# buck4.net
KiCad netlist of a schematic drawn in Altium Designer
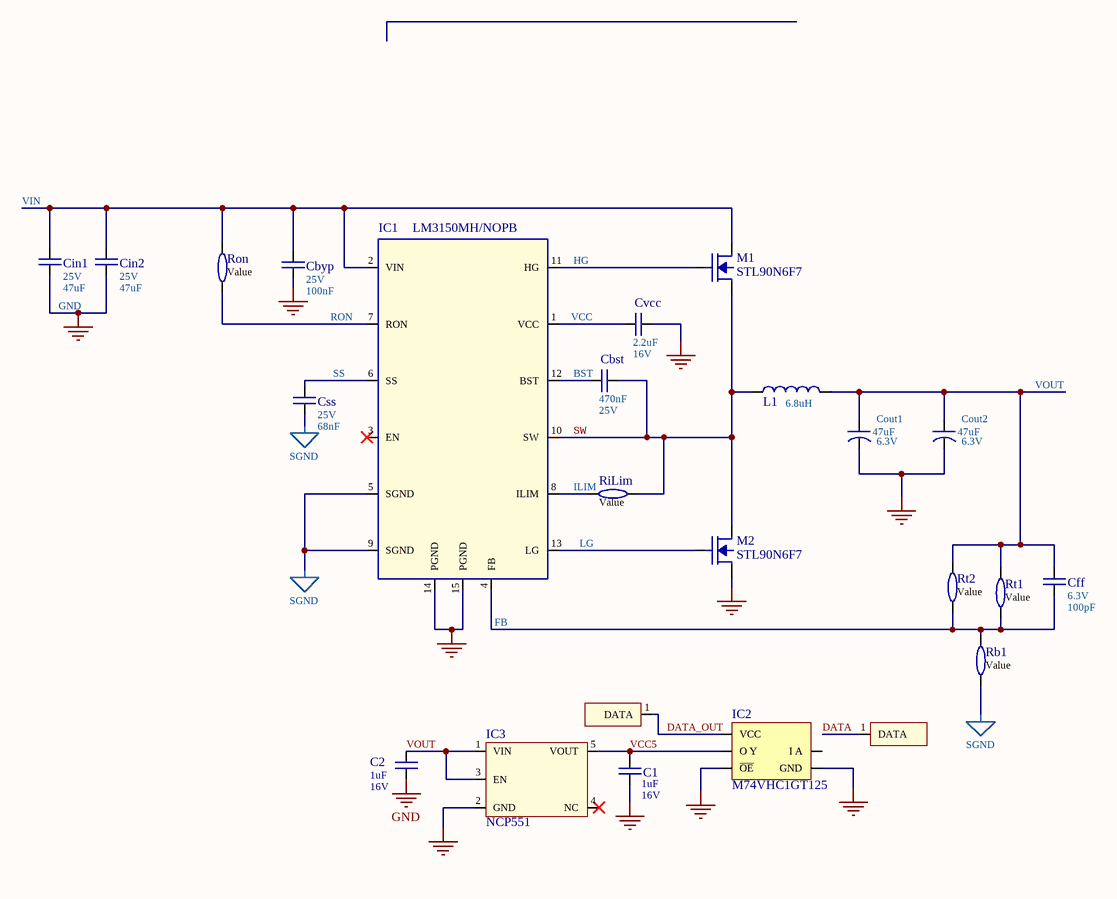
[diagram p0: buck4.schdoc]

(export (version "E")
  (design (tool "Eeschema 10.0.6"))
  (components
    (comp (ref "C1")
      (value "1uF")
      (footprint "CAPC1608X08L")
      (description "Multilayer Ceramic Capacitor")
      (fields (field (name "VOLTAGE") "16V") (field (name "Comment") "MLCC"))
      (libsource (lib "buck4") (part "MLCC"))
    )
    (comp (ref "C2")
      (value "1uF")
      (footprint "CAPC1608X08L")
      (description "Multilayer Ceramic Capacitor")
      (fields (field (name "VOLTAGE") "16V") (field (name "Comment") "MLCC"))
      (libsource (lib "buck4") (part "MLCC"))
    )
    (comp (ref "Cbst")
      (value "470nF")
      (footprint "CAPC1608X08L")
      (description "Multilayer Ceramic Capacitor")
      (fields (field (name "VOLTAGE") "25V") (field (name "Comment") "MLCC"))
      (libsource (lib "buck4") (part "MLCC"))
    )
    (comp (ref "Cbyp")
      (value "100nF")
      (footprint "CAPC2012X12L")
      (description "Multilayer Ceramic Capacitor")
      (fields (field (name "VOLTAGE") "25V") (field (name "Comment") "MLCC"))
      (libsource (lib "buck4") (part "MLCC"))
    )
    (comp (ref "Cff")
      (value "100pF")
      (footprint "CAPC1608X08L")
      (description "Multilayer Ceramic Capacitor")
      (fields (field (name "VOLTAGE") "6.3V") (field (name "Comment") "MLCC"))
      (libsource (lib "buck4") (part "MLCC"))
    )
    (comp (ref "Cin1")
      (value "47uF")
      (footprint "CAPC3225X25L")
      (description "Multilayer Ceramic Capacitor")
      (fields
        (field (name "MPN") "C3216X5R1E476M160AC")
        (field (name "VOLTAGE") "25V")
        (field (name "Comment") "MLCC")
      )
      (libsource (lib "buck4") (part "MLCC"))
    )
    (comp (ref "Cin2")
      (value "47uF")
      (footprint "CAPC3225X25L")
      (description "Multilayer Ceramic Capacitor")
      (fields
        (field (name "MPN") "C3216X5R1E476M160AC")
        (field (name "VOLTAGE") "25V")
        (field (name "Comment") "MLCC")
      )
      (libsource (lib "buck4") (part "MLCC"))
    )
    (comp (ref "Cout1")
      (value "47uF")
      (footprint "CAPMP7343X11L")
      (description "Electrolytic Capacitor")
      (fields
        (field (name "MPN") "EEFCS1A470R")
        (field (name "VOLTAGE") "6.3V")
        (field (name "Comment") "CAPACITOR")
      )
      (libsource (lib "buck4") (part "CAPACITOR"))
    )
    (comp (ref "Cout2")
      (value "47uF")
      (footprint "CAPMP7343X11L")
      (description "Electrolytic Capacitor")
      (fields
        (field (name "MPN") "EEFCS1A470R")
        (field (name "VOLTAGE") "6.3V")
        (field (name "Comment") "CAPACITOR")
      )
      (libsource (lib "buck4") (part "CAPACITOR"))
    )
    (comp (ref "Css")
      (value "68nF")
      (footprint "CAPC1608X08L")
      (description "Multilayer Ceramic Capacitor")
      (fields (field (name "VOLTAGE") "25V") (field (name "Comment") "MLCC"))
      (libsource (lib "buck4") (part "MLCC"))
    )
    (comp (ref "Cvcc")
      (value "2.2uF")
      (footprint "CAPC1608X08L")
      (description "Multilayer Ceramic Capacitor")
      (fields (field (name "VOLTAGE") "16V") (field (name "Comment") "MLCC"))
      (libsource (lib "buck4") (part "MLCC"))
    )
    (comp (ref "DP1") (value "DATA_PAD") (footprint "DATA_PAD") (libsource (lib "buck4") (part "DATA_PAD")))
    (comp (ref "DP2") (value "DATA_PAD") (footprint "DATA_PAD") (libsource (lib "") (part "DATA_PAD_1")))
    (comp (ref "IC1")
      (value "LM3150MH/NOPB")
      (footprint "MXA14A")
      (description "Buck controller")
      (libsource (lib "buck4") (part "LM3150MH/NOPB"))
    )
    (comp (ref "IC2")
      (value "M74VHC1GT125")
      (footprint "SC70-5")
      (description "Level shifter non inverting")
      (libsource (lib "controller_8266") (part "M74VHC1GT125"))
    )
    (comp (ref "IC3")
      (value "NCP551")
      (footprint "SOT95P260X90-5L")
      (libsource (lib "buck4") (part "NCP551"))
    )
    (comp (ref "L1")
      (value "6.8uH")
      (footprint "WE-HCI_1335")
      (description "Inductor")
      (fields (field (name "MANUFACTURER_PART_NUMBER") "744313330"))
      (libsource (lib "buck4") (part "744313330"))
    )
    (comp (ref "M1")
      (value "STL90N6F7")
      (footprint "TRANS_NexFET_Q5A")
      (description "N Channel MOSFET")
      (fields (field (name "MANUFACTURER_PART_NUMBER") "CSD17579Q5A"))
      (libsource (lib "buck4") (part "CSD17579Q5A"))
    )
    (comp (ref "M2")
      (value "STL90N6F7")
      (footprint "TRANS_NexFET_Q5A")
      (description "N Channel MOSFET")
      (fields (field (name "MANUFACTURER_PART_NUMBER") "CSD18537NQ5A"))
      (libsource (lib "buck4") (part "CSD18537NQ5A"))
    )
    (comp (ref "Rb1")
      (value "Value")
      (footprint "RESC1608X03L")
      (description "Chip Resistor")
      (fields (field (name "Comment") "RES0603"))
      (libsource (lib "clock") (part "RES0603"))
    )
    (comp (ref "RiLim")
      (value "Value")
      (footprint "RESC1608X03L")
      (description "Chip Resistor")
      (fields (field (name "Comment") "RES0603"))
      (libsource (lib "clock") (part "RES0603"))
    )
    (comp (ref "Ron")
      (value "Value")
      (footprint "RESC1608X03L")
      (description "Chip Resistor")
      (fields (field (name "Comment") "RES0603"))
      (libsource (lib "clock") (part "RES0603"))
    )
    (comp (ref "Rt1")
      (value "Value")
      (footprint "RESC1608X03L")
      (description "Chip Resistor")
      (fields (field (name "Comment") "RES0603"))
      (libsource (lib "clock") (part "RES0603"))
    )
    (comp (ref "Rt2")
      (value "Value")
      (footprint "RESC1608X03L")
      (description "Chip Resistor")
      (fields (field (name "Comment") "RES0603"))
      (libsource (lib "clock") (part "RES0603"))
    )
  )
  (nets
    (net (code "1") (name "/BST") (class "Default")
      (node (ref "Cbst") (pin "1") (pintype "passive"))
      (node (ref "IC1") (pin "12") (pinfunction "BST_12") (pintype "passive"))
    )
    (net (code "2") (name "/DATA") (class "Default")
      (node (ref "DP2") (pin "1") (pinfunction "DATA_1") (pintype "passive"))
    )
    (net (code "3") (name "/DATA_OUT") (class "Default")
      (node (ref "DP1") (pin "1") (pinfunction "DATA_1") (pintype "passive"))
      (node (ref "IC2") (pin "5") (pinfunction "VCC_5") (pintype "power_in"))
    )
    (net (code "4") (name "/FB") (class "Default")
      (node (ref "Cff") (pin "1") (pintype "passive"))
      (node (ref "IC1") (pin "4") (pinfunction "FB_4") (pintype "passive"))
      (node (ref "Rb1") (pin "2") (pinfunction "2_2") (pintype "passive"))
      (node (ref "Rt1") (pin "1") (pinfunction "1_1") (pintype "passive"))
      (node (ref "Rt2") (pin "1") (pinfunction "1_1") (pintype "passive"))
    )
    (net (code "5") (name "/HG") (class "Default")
      (node (ref "IC1") (pin "11") (pinfunction "HG_11") (pintype "passive"))
      (node (ref "M1") (pin "G") (pinfunction "Gate_G") (pintype "passive"))
    )
    (net (code "6") (name "/ILIM") (class "Default")
      (node (ref "IC1") (pin "8") (pinfunction "ILIM_8") (pintype "passive"))
      (node (ref "RiLim") (pin "1") (pinfunction "1_1") (pintype "passive"))
    )
    (net (code "7") (name "/LG") (class "Default")
      (node (ref "IC1") (pin "13") (pinfunction "LG_13") (pintype "passive"))
      (node (ref "M2") (pin "G") (pinfunction "Gate_G") (pintype "passive"))
    )
    (net (code "8") (name "/RON") (class "Default")
      (node (ref "IC1") (pin "7") (pinfunction "RON_7") (pintype "passive"))
      (node (ref "Ron") (pin "2") (pinfunction "2_2") (pintype "passive"))
    )
    (net (code "9") (name "/SS") (class "Default")
      (node (ref "Css") (pin "2") (pintype "passive"))
      (node (ref "IC1") (pin "6") (pinfunction "SS_6") (pintype "passive"))
    )
    (net (code "10") (name "/SW") (class "Default")
      (node (ref "Cbst") (pin "2") (pintype "passive"))
      (node (ref "IC1") (pin "10") (pinfunction "SW_10") (pintype "passive"))
      (node (ref "L1") (pin "2") (pinfunction "2_2") (pintype "passive"))
      (node (ref "M1") (pin "S") (pinfunction "Source_S") (pintype "passive"))
      (node (ref "M2") (pin "D") (pinfunction "Drain_D") (pintype "passive"))
      (node (ref "RiLim") (pin "2") (pinfunction "2_2") (pintype "passive"))
    )
    (net (code "11") (name "/VCC") (class "Default")
      (node (ref "Cvcc") (pin "1") (pintype "passive"))
      (node (ref "IC1") (pin "1") (pinfunction "VCC_1") (pintype "passive"))
    )
    (net (code "12") (name "/VCC5") (class "Default")
      (node (ref "C1") (pin "2") (pintype "passive"))
      (node (ref "IC2") (pin "4") (pinfunction "O_Y_4") (pintype "output"))
      (node (ref "IC3") (pin "5") (pinfunction "VOUT_5") (pintype "passive"))
    )
    (net (code "13") (name "/VIN") (class "Default")
      (node (ref "Cbyp") (pin "2") (pintype "passive"))
      (node (ref "Cin1") (pin "2") (pintype "passive"))
      (node (ref "Cin2") (pin "2") (pintype "passive"))
      (node (ref "IC1") (pin "2") (pinfunction "VIN_2") (pintype "passive"))
      (node (ref "M1") (pin "D") (pinfunction "Drain_D") (pintype "passive"))
      (node (ref "Ron") (pin "1") (pinfunction "1_1") (pintype "passive"))
    )
    (net (code "14") (name "/VOUT") (class "Default")
      (node (ref "C2") (pin "2") (pintype "passive"))
      (node (ref "Cff") (pin "2") (pintype "passive"))
      (node (ref "Cout1") (pin "1") (pinfunction "+_1") (pintype "passive"))
      (node (ref "Cout2") (pin "1") (pinfunction "+_1") (pintype "passive"))
      (node (ref "IC3") (pin "1") (pinfunction "VIN_1") (pintype "power_in"))
      (node (ref "IC3") (pin "3") (pinfunction "EN_3") (pintype "power_in"))
      (node (ref "L1") (pin "1") (pinfunction "1_1") (pintype "passive"))
      (node (ref "Rt1") (pin "2") (pinfunction "2_2") (pintype "passive"))
      (node (ref "Rt2") (pin "2") (pinfunction "2_2") (pintype "passive"))
    )
    (net (code "15") (name "GND") (class "Default")
      (node (ref "C1") (pin "1") (pintype "passive"))
      (node (ref "C2") (pin "1") (pintype "passive"))
      (node (ref "Cbyp") (pin "1") (pintype "passive"))
      (node (ref "Cin1") (pin "1") (pintype "passive"))
      (node (ref "Cin2") (pin "1") (pintype "passive"))
      (node (ref "Cout1") (pin "2") (pinfunction "-_2") (pintype "passive"))
      (node (ref "Cout2") (pin "2") (pinfunction "-_2") (pintype "passive"))
      (node (ref "Cvcc") (pin "2") (pintype "passive"))
      (node (ref "IC1") (pin "14") (pinfunction "PGND_14") (pintype "passive"))
      (node (ref "IC1") (pin "15") (pinfunction "PGND_15") (pintype "passive"))
      (node (ref "IC2") (pin "1") (pinfunction "OE_1") (pintype "input"))
      (node (ref "IC2") (pin "3") (pinfunction "GND_3") (pintype "power_in"))
      (node (ref "IC3") (pin "2") (pinfunction "GND_2") (pintype "power_in"))
      (node (ref "M2") (pin "S") (pinfunction "Source_S") (pintype "passive"))
    )
    (net (code "16") (name "SGND") (class "Default")
      (node (ref "Css") (pin "1") (pintype "passive"))
      (node (ref "IC1") (pin "5") (pinfunction "SGND_5") (pintype "passive"))
      (node (ref "IC1") (pin "9") (pinfunction "SGND_9") (pintype "passive"))
      (node (ref "Rb1") (pin "1") (pinfunction "1_1") (pintype "passive"))
    )
    (net (code "17") (name "unconnected-(IC1-EN-Pad3)") (class "Default")
      (node (ref "IC1") (pin "3") (pinfunction "EN_3") (pintype "passive+no_connect"))
    )
    (net (code "18") (name "unconnected-(IC2-I_A-Pad2)") (class "Default")
      (node (ref "IC2") (pin "2") (pinfunction "I_A_2") (pintype "input"))
    )
    (net (code "19") (name "unconnected-(IC3-NC-Pad4)") (class "Default")
      (node (ref "IC3") (pin "4") (pinfunction "NC_4") (pintype "passive+no_connect"))
    )
  )
)
